# MODULO2.net
KiCad netlist of a schematic drawn in EAGLE
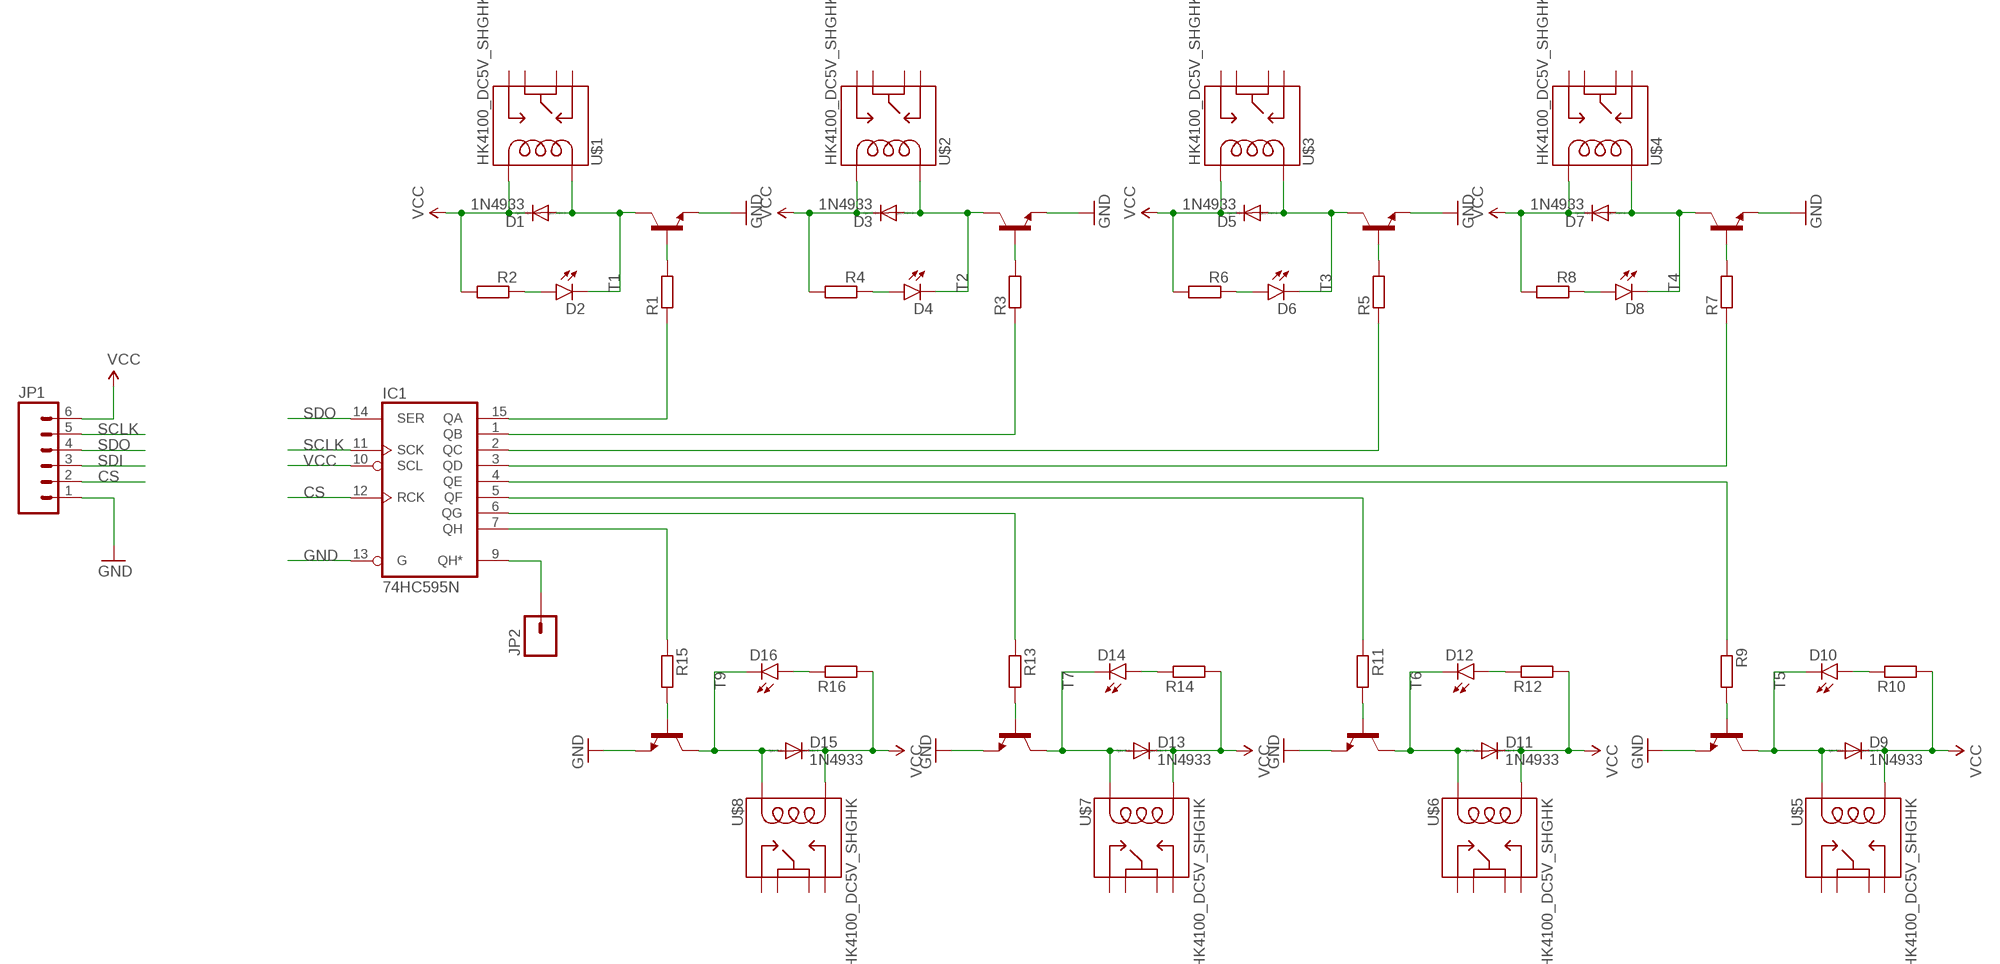
[diagram p0: schematic, sheet 1]

(export (version "E")
  (design (tool "Eeschema 10.0.6"))
  (components
    (comp (ref "D1")
      (value "1N4933")
      (footprint "eagle-import:DO41-10")
      (libsource (lib "eagle-import") (part "1N4933"))
    )
    (comp (ref "D2")
      (value "LED5MM")
      (footprint "eagle-import:LED5MM")
      (libsource (lib "eagle-import") (part "LED5MM"))
    )
    (comp (ref "D3")
      (value "1N4933")
      (footprint "eagle-import:DO41-10")
      (libsource (lib "eagle-import") (part "1N4933"))
    )
    (comp (ref "D4")
      (value "LED5MM")
      (footprint "eagle-import:LED5MM")
      (libsource (lib "eagle-import") (part "LED5MM"))
    )
    (comp (ref "D5")
      (value "1N4933")
      (footprint "eagle-import:DO41-10")
      (libsource (lib "eagle-import") (part "1N4933"))
    )
    (comp (ref "D6")
      (value "LED5MM")
      (footprint "eagle-import:LED5MM")
      (libsource (lib "eagle-import") (part "LED5MM"))
    )
    (comp (ref "D7")
      (value "1N4933")
      (footprint "eagle-import:DO41-10")
      (libsource (lib "eagle-import") (part "1N4933"))
    )
    (comp (ref "D8")
      (value "LED5MM")
      (footprint "eagle-import:LED5MM")
      (libsource (lib "eagle-import") (part "LED5MM"))
    )
    (comp (ref "D9")
      (value "1N4933")
      (footprint "eagle-import:DO41-10")
      (libsource (lib "eagle-import") (part "1N4933"))
    )
    (comp (ref "D10")
      (value "LED5MM")
      (footprint "eagle-import:LED5MM")
      (libsource (lib "eagle-import") (part "LED5MM"))
    )
    (comp (ref "D11")
      (value "1N4933")
      (footprint "eagle-import:DO41-10")
      (libsource (lib "eagle-import") (part "1N4933"))
    )
    (comp (ref "D12")
      (value "LED5MM")
      (footprint "eagle-import:LED5MM")
      (libsource (lib "eagle-import") (part "LED5MM"))
    )
    (comp (ref "D13")
      (value "1N4933")
      (footprint "eagle-import:DO41-10")
      (libsource (lib "eagle-import") (part "1N4933"))
    )
    (comp (ref "D14")
      (value "LED5MM")
      (footprint "eagle-import:LED5MM")
      (libsource (lib "eagle-import") (part "LED5MM"))
    )
    (comp (ref "D15")
      (value "1N4933")
      (footprint "eagle-import:DO41-10")
      (libsource (lib "eagle-import") (part "1N4933"))
    )
    (comp (ref "D16")
      (value "LED5MM")
      (footprint "eagle-import:LED5MM")
      (libsource (lib "eagle-import") (part "LED5MM"))
    )
    (comp (ref "IC1")
      (value "74HC595N")
      (footprint "eagle-import:DIL16")
      (libsource (lib "eagle-import") (part "74595NHC"))
    )
    (comp (ref "JP1")
      (value "M06LOCK")
      (footprint "eagle-import:1X06_LOCK")
      (libsource (lib "eagle-import") (part "M06LOCK"))
    )
    (comp (ref "JP2")
      (value "M01PTH")
      (footprint "eagle-import:1X01")
      (libsource (lib "eagle-import") (part "M01PTH"))
    )
    (comp (ref "R1")
      (value "R-EU_R0805")
      (footprint "eagle-import:R0805")
      (libsource (lib "eagle-import") (part "R-EU_R0805"))
    )
    (comp (ref "R2")
      (value "R-EU_R0805")
      (footprint "eagle-import:R0805")
      (libsource (lib "eagle-import") (part "R-EU_R0805"))
    )
    (comp (ref "R3")
      (value "R-EU_R0805")
      (footprint "eagle-import:R0805")
      (libsource (lib "eagle-import") (part "R-EU_R0805"))
    )
    (comp (ref "R4")
      (value "R-EU_R0805")
      (footprint "eagle-import:R0805")
      (libsource (lib "eagle-import") (part "R-EU_R0805"))
    )
    (comp (ref "R5")
      (value "R-EU_R0805")
      (footprint "eagle-import:R0805")
      (libsource (lib "eagle-import") (part "R-EU_R0805"))
    )
    (comp (ref "R6")
      (value "R-EU_R0805")
      (footprint "eagle-import:R0805")
      (libsource (lib "eagle-import") (part "R-EU_R0805"))
    )
    (comp (ref "R7")
      (value "R-EU_R0805")
      (footprint "eagle-import:R0805")
      (libsource (lib "eagle-import") (part "R-EU_R0805"))
    )
    (comp (ref "R8")
      (value "R-EU_R0805")
      (footprint "eagle-import:R0805")
      (libsource (lib "eagle-import") (part "R-EU_R0805"))
    )
    (comp (ref "R9")
      (value "R-EU_R0805")
      (footprint "eagle-import:R0805")
      (libsource (lib "eagle-import") (part "R-EU_R0805"))
    )
    (comp (ref "R10")
      (value "R-EU_R0805")
      (footprint "eagle-import:R0805")
      (libsource (lib "eagle-import") (part "R-EU_R0805"))
    )
    (comp (ref "R11")
      (value "R-EU_R0805")
      (footprint "eagle-import:R0805")
      (libsource (lib "eagle-import") (part "R-EU_R0805"))
    )
    (comp (ref "R12")
      (value "R-EU_R0805")
      (footprint "eagle-import:R0805")
      (libsource (lib "eagle-import") (part "R-EU_R0805"))
    )
    (comp (ref "R13")
      (value "R-EU_R0805")
      (footprint "eagle-import:R0805")
      (libsource (lib "eagle-import") (part "R-EU_R0805"))
    )
    (comp (ref "R14")
      (value "R-EU_R0805")
      (footprint "eagle-import:R0805")
      (libsource (lib "eagle-import") (part "R-EU_R0805"))
    )
    (comp (ref "R15")
      (value "R-EU_R0805")
      (footprint "eagle-import:R0805")
      (libsource (lib "eagle-import") (part "R-EU_R0805"))
    )
    (comp (ref "R16")
      (value "R-EU_R0805")
      (footprint "eagle-import:R0805")
      (libsource (lib "eagle-import") (part "R-EU_R0805"))
    )
    (comp (ref "T1")
      (value "-NPN-TO92-EBC")
      (footprint "eagle-import:TO92-EBC")
      (libsource (lib "eagle-import") (part "-NPN-TO92-EBC"))
    )
    (comp (ref "T2")
      (value "-NPN-TO92-EBC")
      (footprint "eagle-import:TO92-EBC")
      (libsource (lib "eagle-import") (part "-NPN-TO92-EBC"))
    )
    (comp (ref "T3")
      (value "-NPN-TO92-EBC")
      (footprint "eagle-import:TO92-EBC")
      (libsource (lib "eagle-import") (part "-NPN-TO92-EBC"))
    )
    (comp (ref "T4")
      (value "-NPN-TO92-EBC")
      (footprint "eagle-import:TO92-EBC")
      (libsource (lib "eagle-import") (part "-NPN-TO92-EBC"))
    )
    (comp (ref "T5")
      (value "-NPN-TO92-EBC")
      (footprint "eagle-import:TO92-EBC")
      (libsource (lib "eagle-import") (part "-NPN-TO92-EBC"))
    )
    (comp (ref "T6")
      (value "-NPN-TO92-EBC")
      (footprint "eagle-import:TO92-EBC")
      (libsource (lib "eagle-import") (part "-NPN-TO92-EBC"))
    )
    (comp (ref "T7")
      (value "-NPN-TO92-EBC")
      (footprint "eagle-import:TO92-EBC")
      (libsource (lib "eagle-import") (part "-NPN-TO92-EBC"))
    )
    (comp (ref "T9")
      (value "-NPN-TO92-EBC")
      (footprint "eagle-import:TO92-EBC")
      (libsource (lib "eagle-import") (part "-NPN-TO92-EBC"))
    )
    (comp (ref "U$1")
      (value "HK4100_DC5V_SHGHK")
      (footprint "eagle-import:HK4100")
      (libsource (lib "eagle-import") (part "HK4100_DC5V_SHGHK"))
    )
    (comp (ref "U$2")
      (value "HK4100_DC5V_SHGHK")
      (footprint "eagle-import:HK4100")
      (libsource (lib "eagle-import") (part "HK4100_DC5V_SHGHK"))
    )
    (comp (ref "U$3")
      (value "HK4100_DC5V_SHGHK")
      (footprint "eagle-import:HK4100")
      (libsource (lib "eagle-import") (part "HK4100_DC5V_SHGHK"))
    )
    (comp (ref "U$4")
      (value "HK4100_DC5V_SHGHK")
      (footprint "eagle-import:HK4100")
      (libsource (lib "eagle-import") (part "HK4100_DC5V_SHGHK"))
    )
    (comp (ref "U$5")
      (value "HK4100_DC5V_SHGHK")
      (footprint "eagle-import:HK4100")
      (libsource (lib "eagle-import") (part "HK4100_DC5V_SHGHK"))
    )
    (comp (ref "U$6")
      (value "HK4100_DC5V_SHGHK")
      (footprint "eagle-import:HK4100")
      (libsource (lib "eagle-import") (part "HK4100_DC5V_SHGHK"))
    )
    (comp (ref "U$7")
      (value "HK4100_DC5V_SHGHK")
      (footprint "eagle-import:HK4100")
      (libsource (lib "eagle-import") (part "HK4100_DC5V_SHGHK"))
    )
    (comp (ref "U$8")
      (value "HK4100_DC5V_SHGHK")
      (footprint "eagle-import:HK4100")
      (libsource (lib "eagle-import") (part "HK4100_DC5V_SHGHK"))
    )
  )
  (nets
    (net (code "1") (name "/CS") (class "Default")
      (node (ref "IC1") (pin "12") (pinfunction "RCK_12") (pintype "input"))
      (node (ref "JP1") (pin "2") (pinfunction "2_2") (pintype "passive"))
    )
    (net (code "2") (name "/SCLK") (class "Default")
      (node (ref "IC1") (pin "11") (pinfunction "SCK_11") (pintype "input"))
      (node (ref "JP1") (pin "5") (pinfunction "5_5") (pintype "passive"))
    )
    (net (code "3") (name "/SDI") (class "Default")
      (node (ref "JP1") (pin "3") (pinfunction "3_3") (pintype "passive"))
    )
    (net (code "4") (name "/SDO") (class "Default")
      (node (ref "IC1") (pin "14") (pinfunction "SER_14") (pintype "input"))
      (node (ref "JP1") (pin "4") (pinfunction "4_4") (pintype "passive"))
    )
    (net (code "5") (name "GND") (class "Default")
      (node (ref "IC1") (pin "13") (pinfunction "G_13") (pintype "input"))
      (node (ref "JP1") (pin "1") (pinfunction "1_1") (pintype "passive"))
      (node (ref "T1") (pin "E") (pinfunction "E_E") (pintype "passive"))
      (node (ref "T2") (pin "E") (pinfunction "E_E") (pintype "passive"))
      (node (ref "T3") (pin "E") (pinfunction "E_E") (pintype "passive"))
      (node (ref "T4") (pin "E") (pinfunction "E_E") (pintype "passive"))
      (node (ref "T5") (pin "E") (pinfunction "E_E") (pintype "passive"))
      (node (ref "T6") (pin "E") (pinfunction "E_E") (pintype "passive"))
      (node (ref "T7") (pin "E") (pinfunction "E_E") (pintype "passive"))
      (node (ref "T9") (pin "E") (pinfunction "E_E") (pintype "passive"))
    )
    (net (code "6") (name "Net-(D2-C)") (class "Default")
      (node (ref "D1") (pin "A") (pinfunction "A_A") (pintype "passive"))
      (node (ref "D2") (pin "K") (pinfunction "C_K") (pintype "passive"))
      (node (ref "T1") (pin "C") (pinfunction "C_C") (pintype "passive"))
      (node (ref "U$1") (pin "6") (pinfunction "2_6") (pintype "bidirectional"))
    )
    (net (code "7") (name "Net-(D2-PadA)") (class "Default")
      (node (ref "D2") (pin "A") (pinfunction "A_A") (pintype "passive"))
      (node (ref "R2") (pin "1") (pinfunction "1_1") (pintype "passive"))
    )
    (net (code "8") (name "Net-(D4-C)") (class "Default")
      (node (ref "D3") (pin "A") (pinfunction "A_A") (pintype "passive"))
      (node (ref "D4") (pin "K") (pinfunction "C_K") (pintype "passive"))
      (node (ref "T2") (pin "C") (pinfunction "C_C") (pintype "passive"))
      (node (ref "U$2") (pin "6") (pinfunction "2_6") (pintype "bidirectional"))
    )
    (net (code "9") (name "Net-(D4-PadA)") (class "Default")
      (node (ref "D4") (pin "A") (pinfunction "A_A") (pintype "passive"))
      (node (ref "R4") (pin "1") (pinfunction "1_1") (pintype "passive"))
    )
    (net (code "10") (name "Net-(D6-C)") (class "Default")
      (node (ref "D5") (pin "A") (pinfunction "A_A") (pintype "passive"))
      (node (ref "D6") (pin "K") (pinfunction "C_K") (pintype "passive"))
      (node (ref "T3") (pin "C") (pinfunction "C_C") (pintype "passive"))
      (node (ref "U$3") (pin "6") (pinfunction "2_6") (pintype "bidirectional"))
    )
    (net (code "11") (name "Net-(D6-PadA)") (class "Default")
      (node (ref "D6") (pin "A") (pinfunction "A_A") (pintype "passive"))
      (node (ref "R6") (pin "1") (pinfunction "1_1") (pintype "passive"))
    )
    (net (code "12") (name "Net-(D8-C)") (class "Default")
      (node (ref "D7") (pin "A") (pinfunction "A_A") (pintype "passive"))
      (node (ref "D8") (pin "K") (pinfunction "C_K") (pintype "passive"))
      (node (ref "T4") (pin "C") (pinfunction "C_C") (pintype "passive"))
      (node (ref "U$4") (pin "6") (pinfunction "2_6") (pintype "bidirectional"))
    )
    (net (code "13") (name "Net-(D8-PadA)") (class "Default")
      (node (ref "D8") (pin "A") (pinfunction "A_A") (pintype "passive"))
      (node (ref "R8") (pin "1") (pinfunction "1_1") (pintype "passive"))
    )
    (net (code "14") (name "Net-(D10-C)") (class "Default")
      (node (ref "D10") (pin "K") (pinfunction "C_K") (pintype "passive"))
      (node (ref "D9") (pin "A") (pinfunction "A_A") (pintype "passive"))
      (node (ref "T5") (pin "C") (pinfunction "C_C") (pintype "passive"))
      (node (ref "U$5") (pin "6") (pinfunction "2_6") (pintype "bidirectional"))
    )
    (net (code "15") (name "Net-(D10-PadA)") (class "Default")
      (node (ref "D10") (pin "A") (pinfunction "A_A") (pintype "passive"))
      (node (ref "R10") (pin "1") (pinfunction "1_1") (pintype "passive"))
    )
    (net (code "16") (name "Net-(D12-C)") (class "Default")
      (node (ref "D11") (pin "A") (pinfunction "A_A") (pintype "passive"))
      (node (ref "D12") (pin "K") (pinfunction "C_K") (pintype "passive"))
      (node (ref "T6") (pin "C") (pinfunction "C_C") (pintype "passive"))
      (node (ref "U$6") (pin "6") (pinfunction "2_6") (pintype "bidirectional"))
    )
    (net (code "17") (name "Net-(D12-PadA)") (class "Default")
      (node (ref "D12") (pin "A") (pinfunction "A_A") (pintype "passive"))
      (node (ref "R12") (pin "1") (pinfunction "1_1") (pintype "passive"))
    )
    (net (code "18") (name "Net-(D14-C)") (class "Default")
      (node (ref "D13") (pin "A") (pinfunction "A_A") (pintype "passive"))
      (node (ref "D14") (pin "K") (pinfunction "C_K") (pintype "passive"))
      (node (ref "T7") (pin "C") (pinfunction "C_C") (pintype "passive"))
      (node (ref "U$7") (pin "6") (pinfunction "2_6") (pintype "bidirectional"))
    )
    (net (code "19") (name "Net-(D14-PadA)") (class "Default")
      (node (ref "D14") (pin "A") (pinfunction "A_A") (pintype "passive"))
      (node (ref "R14") (pin "1") (pinfunction "1_1") (pintype "passive"))
    )
    (net (code "20") (name "Net-(D16-C)") (class "Default")
      (node (ref "D15") (pin "A") (pinfunction "A_A") (pintype "passive"))
      (node (ref "D16") (pin "K") (pinfunction "C_K") (pintype "passive"))
      (node (ref "T9") (pin "C") (pinfunction "C_C") (pintype "passive"))
      (node (ref "U$8") (pin "6") (pinfunction "2_6") (pintype "bidirectional"))
    )
    (net (code "21") (name "Net-(D16-PadA)") (class "Default")
      (node (ref "D16") (pin "A") (pinfunction "A_A") (pintype "passive"))
      (node (ref "R16") (pin "1") (pinfunction "1_1") (pintype "passive"))
    )
    (net (code "22") (name "Net-(IC1A-QA)") (class "Default")
      (node (ref "IC1") (pin "15") (pinfunction "QA_15") (pintype "tri_state"))
      (node (ref "R1") (pin "1") (pinfunction "1_1") (pintype "passive"))
    )
    (net (code "23") (name "Net-(IC1A-QB)") (class "Default")
      (node (ref "IC1") (pin "1") (pinfunction "QB_1") (pintype "tri_state"))
      (node (ref "R3") (pin "1") (pinfunction "1_1") (pintype "passive"))
    )
    (net (code "24") (name "Net-(IC1A-QC)") (class "Default")
      (node (ref "IC1") (pin "2") (pinfunction "QC_2") (pintype "tri_state"))
      (node (ref "R5") (pin "1") (pinfunction "1_1") (pintype "passive"))
    )
    (net (code "25") (name "Net-(IC1A-QD)") (class "Default")
      (node (ref "IC1") (pin "3") (pinfunction "QD_3") (pintype "tri_state"))
      (node (ref "R7") (pin "1") (pinfunction "1_1") (pintype "passive"))
    )
    (net (code "26") (name "Net-(IC1A-QE)") (class "Default")
      (node (ref "IC1") (pin "4") (pinfunction "QE_4") (pintype "tri_state"))
      (node (ref "R9") (pin "1") (pinfunction "1_1") (pintype "passive"))
    )
    (net (code "27") (name "Net-(IC1A-QF)") (class "Default")
      (node (ref "IC1") (pin "5") (pinfunction "QF_5") (pintype "tri_state"))
      (node (ref "R11") (pin "1") (pinfunction "1_1") (pintype "passive"))
    )
    (net (code "28") (name "Net-(IC1A-QG)") (class "Default")
      (node (ref "IC1") (pin "6") (pinfunction "QG_6") (pintype "tri_state"))
      (node (ref "R13") (pin "1") (pinfunction "1_1") (pintype "passive"))
    )
    (net (code "29") (name "Net-(IC1A-QH)") (class "Default")
      (node (ref "IC1") (pin "7") (pinfunction "QH_7") (pintype "tri_state"))
      (node (ref "R15") (pin "1") (pinfunction "1_1") (pintype "passive"))
    )
    (net (code "30") (name "Net-(IC1A-QH*)") (class "Default")
      (node (ref "IC1") (pin "9") (pinfunction "QH*_9") (pintype "tri_state"))
      (node (ref "JP2") (pin "1") (pinfunction "1_1") (pintype "passive"))
    )
    (net (code "31") (name "Net-(R1-Pad2)") (class "Default")
      (node (ref "R1") (pin "2") (pinfunction "2_2") (pintype "passive"))
      (node (ref "T1") (pin "B") (pinfunction "B_B") (pintype "passive"))
    )
    (net (code "32") (name "Net-(R3-Pad2)") (class "Default")
      (node (ref "R3") (pin "2") (pinfunction "2_2") (pintype "passive"))
      (node (ref "T2") (pin "B") (pinfunction "B_B") (pintype "passive"))
    )
    (net (code "33") (name "Net-(R5-Pad2)") (class "Default")
      (node (ref "R5") (pin "2") (pinfunction "2_2") (pintype "passive"))
      (node (ref "T3") (pin "B") (pinfunction "B_B") (pintype "passive"))
    )
    (net (code "34") (name "Net-(R7-Pad2)") (class "Default")
      (node (ref "R7") (pin "2") (pinfunction "2_2") (pintype "passive"))
      (node (ref "T4") (pin "B") (pinfunction "B_B") (pintype "passive"))
    )
    (net (code "35") (name "Net-(R9-Pad2)") (class "Default")
      (node (ref "R9") (pin "2") (pinfunction "2_2") (pintype "passive"))
      (node (ref "T5") (pin "B") (pinfunction "B_B") (pintype "passive"))
    )
    (net (code "36") (name "Net-(R11-Pad2)") (class "Default")
      (node (ref "R11") (pin "2") (pinfunction "2_2") (pintype "passive"))
      (node (ref "T6") (pin "B") (pinfunction "B_B") (pintype "passive"))
    )
    (net (code "37") (name "Net-(R13-Pad2)") (class "Default")
      (node (ref "R13") (pin "2") (pinfunction "2_2") (pintype "passive"))
      (node (ref "T7") (pin "B") (pinfunction "B_B") (pintype "passive"))
    )
    (net (code "38") (name "Net-(R15-Pad2)") (class "Default")
      (node (ref "R15") (pin "2") (pinfunction "2_2") (pintype "passive"))
      (node (ref "T9") (pin "B") (pinfunction "B_B") (pintype "passive"))
    )
    (net (code "39") (name "VCC") (class "Default")
      (node (ref "D1") (pin "C") (pinfunction "C_C") (pintype "passive"))
      (node (ref "D11") (pin "C") (pinfunction "C_C") (pintype "passive"))
      (node (ref "D13") (pin "C") (pinfunction "C_C") (pintype "passive"))
      (node (ref "D15") (pin "C") (pinfunction "C_C") (pintype "passive"))
      (node (ref "D3") (pin "C") (pinfunction "C_C") (pintype "passive"))
      (node (ref "D5") (pin "C") (pinfunction "C_C") (pintype "passive"))
      (node (ref "D7") (pin "C") (pinfunction "C_C") (pintype "passive"))
      (node (ref "D9") (pin "C") (pinfunction "C_C") (pintype "passive"))
      (node (ref "IC1") (pin "10") (pinfunction "SCL_10") (pintype "input"))
      (node (ref "JP1") (pin "6") (pinfunction "6_6") (pintype "passive"))
      (node (ref "R10") (pin "2") (pinfunction "2_2") (pintype "passive"))
      (node (ref "R12") (pin "2") (pinfunction "2_2") (pintype "passive"))
      (node (ref "R14") (pin "2") (pinfunction "2_2") (pintype "passive"))
      (node (ref "R16") (pin "2") (pinfunction "2_2") (pintype "passive"))
      (node (ref "R2") (pin "2") (pinfunction "2_2") (pintype "passive"))
      (node (ref "R4") (pin "2") (pinfunction "2_2") (pintype "passive"))
      (node (ref "R6") (pin "2") (pinfunction "2_2") (pintype "passive"))
      (node (ref "R8") (pin "2") (pinfunction "2_2") (pintype "passive"))
      (node (ref "U$1") (pin "9") (pinfunction "9_9") (pintype "bidirectional"))
      (node (ref "U$2") (pin "9") (pinfunction "9_9") (pintype "bidirectional"))
      (node (ref "U$3") (pin "9") (pinfunction "9_9") (pintype "bidirectional"))
      (node (ref "U$4") (pin "9") (pinfunction "9_9") (pintype "bidirectional"))
      (node (ref "U$5") (pin "9") (pinfunction "9_9") (pintype "bidirectional"))
      (node (ref "U$6") (pin "9") (pinfunction "9_9") (pintype "bidirectional"))
      (node (ref "U$7") (pin "9") (pinfunction "9_9") (pintype "bidirectional"))
      (node (ref "U$8") (pin "9") (pinfunction "9_9") (pintype "bidirectional"))
    )
    (net (code "40") (name "unconnected-(U$1-1-Pad7)") (class "Default")
      (node (ref "U$1") (pin "7") (pinfunction "1_7") (pintype "bidirectional"))
    )
    (net (code "41") (name "unconnected-(U$1-5-Pad1)") (class "Default")
      (node (ref "U$1") (pin "1") (pinfunction "5_1") (pintype "bidirectional"))
    )
    (net (code "42") (name "unconnected-(U$1-6-Pad14)") (class "Default")
      (node (ref "U$1") (pin "14") (pinfunction "6_14") (pintype "bidirectional"))
    )
    (net (code "43") (name "unconnected-(U$1-10-Pad8)") (class "Default")
      (node (ref "U$1") (pin "8") (pinfunction "10_8") (pintype "bidirectional"))
    )
    (net (code "44") (name "unconnected-(U$2-1-Pad7)") (class "Default")
      (node (ref "U$2") (pin "7") (pinfunction "1_7") (pintype "bidirectional"))
    )
    (net (code "45") (name "unconnected-(U$2-5-Pad1)") (class "Default")
      (node (ref "U$2") (pin "1") (pinfunction "5_1") (pintype "bidirectional"))
    )
    (net (code "46") (name "unconnected-(U$2-6-Pad14)") (class "Default")
      (node (ref "U$2") (pin "14") (pinfunction "6_14") (pintype "bidirectional"))
    )
    (net (code "47") (name "unconnected-(U$2-10-Pad8)") (class "Default")
      (node (ref "U$2") (pin "8") (pinfunction "10_8") (pintype "bidirectional"))
    )
    (net (code "48") (name "unconnected-(U$3-1-Pad7)") (class "Default")
      (node (ref "U$3") (pin "7") (pinfunction "1_7") (pintype "bidirectional"))
    )
    (net (code "49") (name "unconnected-(U$3-5-Pad1)") (class "Default")
      (node (ref "U$3") (pin "1") (pinfunction "5_1") (pintype "bidirectional"))
    )
    (net (code "50") (name "unconnected-(U$3-6-Pad14)") (class "Default")
      (node (ref "U$3") (pin "14") (pinfunction "6_14") (pintype "bidirectional"))
    )
    (net (code "51") (name "unconnected-(U$3-10-Pad8)") (class "Default")
      (node (ref "U$3") (pin "8") (pinfunction "10_8") (pintype "bidirectional"))
    )
    (net (code "52") (name "unconnected-(U$4-1-Pad7)") (class "Default")
      (node (ref "U$4") (pin "7") (pinfunction "1_7") (pintype "bidirectional"))
    )
    (net (code "53") (name "unconnected-(U$4-5-Pad1)") (class "Default")
      (node (ref "U$4") (pin "1") (pinfunction "5_1") (pintype "bidirectional"))
    )
    (net (code "54") (name "unconnected-(U$4-6-Pad14)") (class "Default")
      (node (ref "U$4") (pin "14") (pinfunction "6_14") (pintype "bidirectional"))
    )
    (net (code "55") (name "unconnected-(U$4-10-Pad8)") (class "Default")
      (node (ref "U$4") (pin "8") (pinfunction "10_8") (pintype "bidirectional"))
    )
    (net (code "56") (name "unconnected-(U$5-1-Pad7)") (class "Default")
      (node (ref "U$5") (pin "7") (pinfunction "1_7") (pintype "bidirectional"))
    )
    (net (code "57") (name "unconnected-(U$5-5-Pad1)") (class "Default")
      (node (ref "U$5") (pin "1") (pinfunction "5_1") (pintype "bidirectional"))
    )
    (net (code "58") (name "unconnected-(U$5-6-Pad14)") (class "Default")
      (node (ref "U$5") (pin "14") (pinfunction "6_14") (pintype "bidirectional"))
    )
    (net (code "59") (name "unconnected-(U$5-10-Pad8)") (class "Default")
      (node (ref "U$5") (pin "8") (pinfunction "10_8") (pintype "bidirectional"))
    )
    (net (code "60") (name "unconnected-(U$6-1-Pad7)") (class "Default")
      (node (ref "U$6") (pin "7") (pinfunction "1_7") (pintype "bidirectional"))
    )
    (net (code "61") (name "unconnected-(U$6-5-Pad1)") (class "Default")
      (node (ref "U$6") (pin "1") (pinfunction "5_1") (pintype "bidirectional"))
    )
    (net (code "62") (name "unconnected-(U$6-6-Pad14)") (class "Default")
      (node (ref "U$6") (pin "14") (pinfunction "6_14") (pintype "bidirectional"))
    )
    (net (code "63") (name "unconnected-(U$6-10-Pad8)") (class "Default")
      (node (ref "U$6") (pin "8") (pinfunction "10_8") (pintype "bidirectional"))
    )
    (net (code "64") (name "unconnected-(U$7-1-Pad7)") (class "Default")
      (node (ref "U$7") (pin "7") (pinfunction "1_7") (pintype "bidirectional"))
    )
    (net (code "65") (name "unconnected-(U$7-5-Pad1)") (class "Default")
      (node (ref "U$7") (pin "1") (pinfunction "5_1") (pintype "bidirectional"))
    )
    (net (code "66") (name "unconnected-(U$7-6-Pad14)") (class "Default")
      (node (ref "U$7") (pin "14") (pinfunction "6_14") (pintype "bidirectional"))
    )
    (net (code "67") (name "unconnected-(U$7-10-Pad8)") (class "Default")
      (node (ref "U$7") (pin "8") (pinfunction "10_8") (pintype "bidirectional"))
    )
    (net (code "68") (name "unconnected-(U$8-1-Pad7)") (class "Default")
      (node (ref "U$8") (pin "7") (pinfunction "1_7") (pintype "bidirectional"))
    )
    (net (code "69") (name "unconnected-(U$8-5-Pad1)") (class "Default")
      (node (ref "U$8") (pin "1") (pinfunction "5_1") (pintype "bidirectional"))
    )
    (net (code "70") (name "unconnected-(U$8-6-Pad14)") (class "Default")
      (node (ref "U$8") (pin "14") (pinfunction "6_14") (pintype "bidirectional"))
    )
    (net (code "71") (name "unconnected-(U$8-10-Pad8)") (class "Default")
      (node (ref "U$8") (pin "8") (pinfunction "10_8") (pintype "bidirectional"))
    )
  )
)
